# RS485.net
KiCad netlist of a schematic drawn in Altium Designer
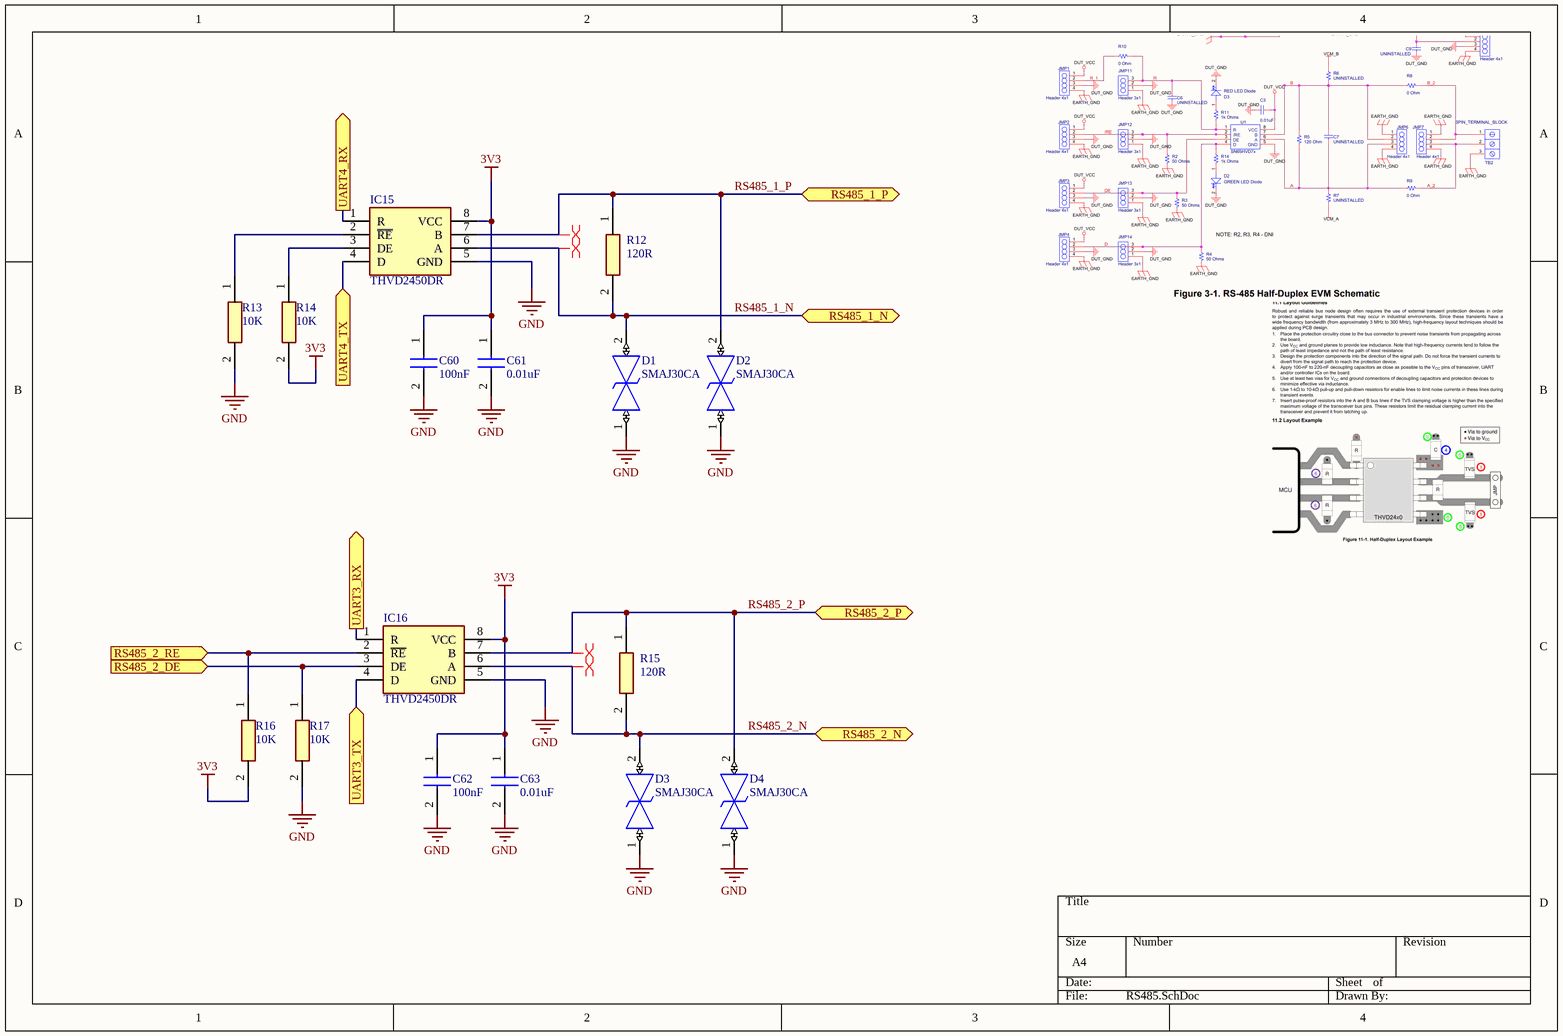
[diagram p0: RS485.SchDoc]

(export (version "E")
  (design (tool "Eeschema 10.0.6"))
  (components
    (comp (ref "C60")
      (value "100nF")
      (footprint "RT_IS:CAPC1608X95N")
      (description "0.1 µF ±20% 16V Ceramic Capacitor X7R 0603 (1608 Metric)")
      (fields (field (name "MANUFACTURER_PART_NUMBER") "C0603C104M4RAC7867"))
      (libsource (lib "*") (part "C0603C104M4RAC7867"))
    )
    (comp (ref "C61")
      (value "0.01uF")
      (footprint "RT_IS:C0603")
      (description "10000 pF ±10% 63V Ceramic Capacitor X7R 0603 (1608 Metric)")
      (fields
        (field (name "MANUFACTURER_PART_NUMBER") "C0603C103KMRECAUTO")
        (field (name "MOUSER PART NUMBER") "80-C0603C103KMREAUTO")
      )
      (libsource (lib "*") (part "C0603C103KMRECAUTO"))
    )
    (comp (ref "C62")
      (value "100nF")
      (footprint "RT_IS:CAPC1608X95N")
      (description "0.1 µF ±20% 16V Ceramic Capacitor X7R 0603 (1608 Metric)")
      (fields (field (name "MANUFACTURER_PART_NUMBER") "C0603C104M4RAC7867"))
      (libsource (lib "*") (part "C0603C104M4RAC7867"))
    )
    (comp (ref "C63")
      (value "0.01uF")
      (footprint "RT_IS:C0603")
      (description "10000 pF ±10% 63V Ceramic Capacitor X7R 0603 (1608 Metric)")
      (fields
        (field (name "MANUFACTURER_PART_NUMBER") "C0603C103KMRECAUTO")
        (field (name "MOUSER PART NUMBER") "80-C0603C103KMREAUTO")
      )
      (libsource (lib "*") (part "C0603C103KMRECAUTO"))
    )
    (comp (ref "D1")
      (value "SMAJ30CA")
      (footprint "RT_IS:DIONM5026X229N")
      (description "48.4V Clamp 8.3A Ipp Tvs Diode Surface Mount DO-214AC (SMA)")
      (fields (field (name "MOUSER PART NUMBER") "576-SMAJ30CA"))
      (libsource (lib "*") (part "SMAJ30CA"))
    )
    (comp (ref "D2")
      (value "SMAJ30CA")
      (footprint "RT_IS:DIONM5026X229N")
      (description "48.4V Clamp 8.3A Ipp Tvs Diode Surface Mount DO-214AC (SMA)")
      (fields (field (name "MOUSER PART NUMBER") "576-SMAJ30CA"))
      (libsource (lib "*") (part "SMAJ30CA"))
    )
    (comp (ref "D3")
      (value "SMAJ30CA")
      (footprint "RT_IS:DIONM5026X229N")
      (description "48.4V Clamp 8.3A Ipp Tvs Diode Surface Mount DO-214AC (SMA)")
      (fields (field (name "MOUSER PART NUMBER") "576-SMAJ30CA"))
      (libsource (lib "*") (part "SMAJ30CA"))
    )
    (comp (ref "D4")
      (value "SMAJ30CA")
      (footprint "RT_IS:DIONM5026X229N")
      (description "48.4V Clamp 8.3A Ipp Tvs Diode Surface Mount DO-214AC (SMA)")
      (fields (field (name "MOUSER PART NUMBER") "576-SMAJ30CA"))
      (libsource (lib "*") (part "SMAJ30CA"))
    )
    (comp (ref "IC15")
      (value "THVD2450DR")
      (footprint "RT_IS:SOIC127P600X175-8N")
      (description "1/1 Transceiver Half RS485 8-SOIC")
      (fields (field (name "MOUSER PART NUMBER") "595-THVD2450DR"))
      (libsource (lib "*") (part "THVD2450DR"))
    )
    (comp (ref "IC16")
      (value "THVD2450DR")
      (footprint "RT_IS:SOIC127P600X175-8N")
      (description "1/1 Transceiver Half RS485 8-SOIC")
      (fields (field (name "MOUSER PART NUMBER") "595-THVD2450DR"))
      (libsource (lib "*") (part "THVD2450DR"))
    )
    (comp (ref "R12")
      (value "120R")
      (footprint "RT_IS:ERA6VK")
      (fields
        (field (name "MANUFACTURER_PART_NUMBER") "ERA-6VEB1200V")
        (field (name "MOUSER PART NUMBER") "667-ERA-6VEB1200V")
      )
      (libsource (lib "*") (part "ERA-6VEB1200V"))
    )
    (comp (ref "R13")
      (value "10K")
      (footprint "RT_IS:RESC1508X50N")
      (description "10 kOhms ±1% 0.125W, 1/8W Chip Resistor 0603 (1608 Metric) Anti-Sulfur Thin Film")
      (fields
        (field (name "MANUFACTURER_PART_NUMBER") "RNCP0603FTD10K0")
        (field (name "MOUSER PART NUMBER") "708-RNCP0603FTD10K0")
      )
      (libsource (lib "*") (part "RNCP0603FTD10K0"))
    )
    (comp (ref "R14")
      (value "10K")
      (footprint "RT_IS:RESC1508X50N")
      (description "10 kOhms ±1% 0.125W, 1/8W Chip Resistor 0603 (1608 Metric) Anti-Sulfur Thin Film")
      (fields
        (field (name "MANUFACTURER_PART_NUMBER") "RNCP0603FTD10K0")
        (field (name "MOUSER PART NUMBER") "708-RNCP0603FTD10K0")
      )
      (libsource (lib "*") (part "RNCP0603FTD10K0"))
    )
    (comp (ref "R15")
      (value "120R")
      (footprint "RT_IS:ERA6VK")
      (fields
        (field (name "MANUFACTURER_PART_NUMBER") "ERA-6VEB1200V")
        (field (name "MOUSER PART NUMBER") "667-ERA-6VEB1200V")
      )
      (libsource (lib "*") (part "ERA-6VEB1200V"))
    )
    (comp (ref "R16")
      (value "10K")
      (footprint "RT_IS:RESC1508X50N")
      (description "10 kOhms ±1% 0.125W, 1/8W Chip Resistor 0603 (1608 Metric) Anti-Sulfur Thin Film")
      (fields
        (field (name "MANUFACTURER_PART_NUMBER") "RNCP0603FTD10K0")
        (field (name "MOUSER PART NUMBER") "708-RNCP0603FTD10K0")
      )
      (libsource (lib "*") (part "RNCP0603FTD10K0"))
    )
    (comp (ref "R17")
      (value "10K")
      (footprint "RT_IS:RESC1508X50N")
      (description "10 kOhms ±1% 0.125W, 1/8W Chip Resistor 0603 (1608 Metric) Anti-Sulfur Thin Film")
      (fields
        (field (name "MANUFACTURER_PART_NUMBER") "RNCP0603FTD10K0")
        (field (name "MOUSER PART NUMBER") "708-RNCP0603FTD10K0")
      )
      (libsource (lib "*") (part "RNCP0603FTD10K0"))
    )
  )
  (nets
    (net (code "1") (name "/RS485_1_N") (class "Default")
      (node (ref "D1") (pin "2") (pinfunction "2_2") (pintype "bidirectional"))
      (node (ref "IC15") (pin "6") (pinfunction "A_6") (pintype "passive"))
      (node (ref "R12") (pin "2") (pinfunction "2_2") (pintype "passive"))
    )
    (net (code "2") (name "/RS485_1_P") (class "Default")
      (node (ref "D2") (pin "2") (pinfunction "2_2") (pintype "bidirectional"))
      (node (ref "IC15") (pin "7") (pinfunction "B_7") (pintype "passive"))
      (node (ref "R12") (pin "1") (pinfunction "1_1") (pintype "passive"))
    )
    (net (code "3") (name "/RS485_2_DE") (class "Default")
      (node (ref "IC16") (pin "3") (pinfunction "DE_3") (pintype "passive"))
      (node (ref "R17") (pin "1") (pinfunction "1_1") (pintype "passive"))
    )
    (net (code "4") (name "/RS485_2_N") (class "Default")
      (node (ref "D3") (pin "2") (pinfunction "2_2") (pintype "bidirectional"))
      (node (ref "IC16") (pin "6") (pinfunction "A_6") (pintype "passive"))
      (node (ref "R15") (pin "2") (pinfunction "2_2") (pintype "passive"))
    )
    (net (code "5") (name "/RS485_2_P") (class "Default")
      (node (ref "D4") (pin "2") (pinfunction "2_2") (pintype "bidirectional"))
      (node (ref "IC16") (pin "7") (pinfunction "B_7") (pintype "passive"))
      (node (ref "R15") (pin "1") (pinfunction "1_1") (pintype "passive"))
    )
    (net (code "6") (name "/RS485_2_RE") (class "Default")
      (node (ref "IC16") (pin "2") (pinfunction "~{RE}_2") (pintype "passive"))
      (node (ref "R16") (pin "1") (pinfunction "1_1") (pintype "passive"))
    )
    (net (code "7") (name "/UART3_RX") (class "Default")
      (node (ref "IC16") (pin "1") (pinfunction "R_1") (pintype "passive"))
    )
    (net (code "8") (name "/UART3_TX") (class "Default")
      (node (ref "IC16") (pin "4") (pinfunction "D_4") (pintype "passive"))
    )
    (net (code "9") (name "/UART4_RX") (class "Default")
      (node (ref "IC15") (pin "1") (pinfunction "R_1") (pintype "passive"))
    )
    (net (code "10") (name "/UART4_TX") (class "Default")
      (node (ref "IC15") (pin "4") (pinfunction "D_4") (pintype "passive"))
    )
    (net (code "11") (name "3V3") (class "Default")
      (node (ref "C60") (pin "1") (pinfunction "1_1") (pintype "passive"))
      (node (ref "C61") (pin "1") (pinfunction "1_1") (pintype "passive"))
      (node (ref "C62") (pin "1") (pinfunction "1_1") (pintype "passive"))
      (node (ref "C63") (pin "1") (pinfunction "1_1") (pintype "passive"))
      (node (ref "IC15") (pin "8") (pinfunction "VCC_8") (pintype "passive"))
      (node (ref "IC16") (pin "8") (pinfunction "VCC_8") (pintype "passive"))
      (node (ref "R14") (pin "2") (pinfunction "2_2") (pintype "passive"))
      (node (ref "R16") (pin "2") (pinfunction "2_2") (pintype "passive"))
    )
    (net (code "12") (name "GND") (class "Default")
      (node (ref "C60") (pin "2") (pinfunction "2_2") (pintype "passive"))
      (node (ref "C61") (pin "2") (pinfunction "2_2") (pintype "passive"))
      (node (ref "C62") (pin "2") (pinfunction "2_2") (pintype "passive"))
      (node (ref "C63") (pin "2") (pinfunction "2_2") (pintype "passive"))
      (node (ref "D1") (pin "1") (pinfunction "1_1") (pintype "bidirectional"))
      (node (ref "D2") (pin "1") (pinfunction "1_1") (pintype "bidirectional"))
      (node (ref "D3") (pin "1") (pinfunction "1_1") (pintype "bidirectional"))
      (node (ref "D4") (pin "1") (pinfunction "1_1") (pintype "bidirectional"))
      (node (ref "IC15") (pin "5") (pinfunction "GND_5") (pintype "passive"))
      (node (ref "IC16") (pin "5") (pinfunction "GND_5") (pintype "passive"))
      (node (ref "R13") (pin "2") (pinfunction "2_2") (pintype "passive"))
      (node (ref "R17") (pin "2") (pinfunction "2_2") (pintype "passive"))
    )
    (net (code "13") (name "Net-(IC15-DE)") (class "Default")
      (node (ref "IC15") (pin "3") (pinfunction "DE_3") (pintype "passive"))
      (node (ref "R14") (pin "1") (pinfunction "1_1") (pintype "passive"))
    )
    (net (code "14") (name "Net-(IC15-~{RE})") (class "Default")
      (node (ref "IC15") (pin "2") (pinfunction "~{RE}_2") (pintype "passive"))
      (node (ref "R13") (pin "1") (pinfunction "1_1") (pintype "passive"))
    )
  )
)
